# Controller.net
KiCad netlist of a schematic drawn in EAGLE
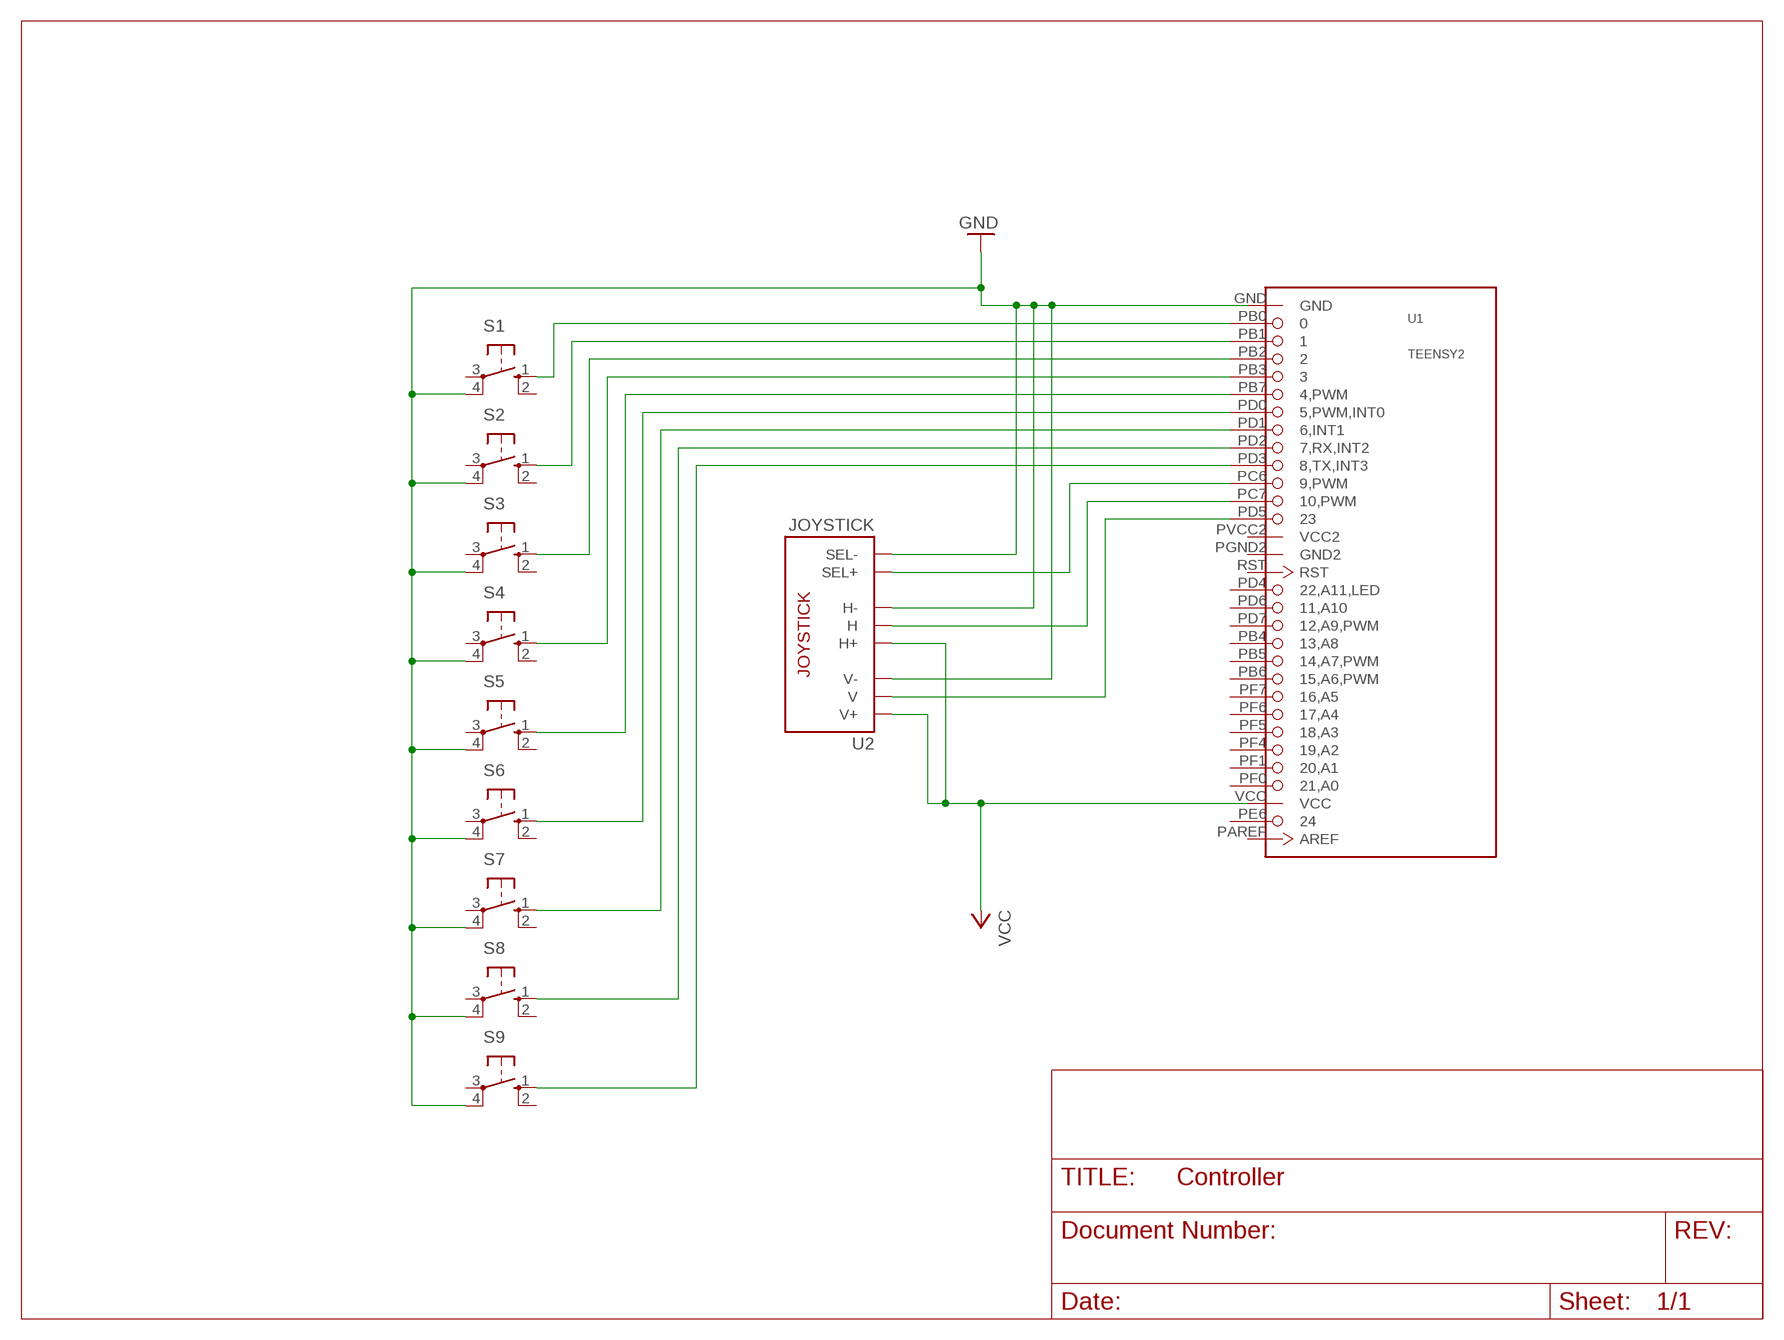
[diagram p0: schematic, sheet 1]

(export (version "E")
  (design (tool "Eeschema 10.0.6"))
  (components
    (comp (ref "S1")
      (value "10-XX")
      (footprint "eagle-import:B3F-10XX")
      (fields (field (name "MPN") "B3F-1000"))
      (libsource (lib "eagle-import") (part "10-XX"))
    )
    (comp (ref "S2")
      (value "10-XX")
      (footprint "eagle-import:B3F-10XX")
      (fields (field (name "MPN") "B3F-1000"))
      (libsource (lib "eagle-import") (part "10-XX"))
    )
    (comp (ref "S3")
      (value "10-XX")
      (footprint "eagle-import:B3F-10XX")
      (fields (field (name "MPN") "B3F-1000"))
      (libsource (lib "eagle-import") (part "10-XX"))
    )
    (comp (ref "S4")
      (value "10-XX")
      (footprint "eagle-import:B3F-10XX")
      (fields (field (name "MPN") "B3F-1000"))
      (libsource (lib "eagle-import") (part "10-XX"))
    )
    (comp (ref "S5")
      (value "10-XX")
      (footprint "eagle-import:B3F-10XX")
      (fields (field (name "MPN") "B3F-1000"))
      (libsource (lib "eagle-import") (part "10-XX"))
    )
    (comp (ref "S6")
      (value "10-XX")
      (footprint "eagle-import:B3F-10XX")
      (fields (field (name "MPN") "B3F-1000"))
      (libsource (lib "eagle-import") (part "10-XX"))
    )
    (comp (ref "S7")
      (value "10-XX")
      (footprint "eagle-import:B3F-10XX")
      (fields (field (name "MPN") "B3F-1000"))
      (libsource (lib "eagle-import") (part "10-XX"))
    )
    (comp (ref "S8")
      (value "10-XX")
      (footprint "eagle-import:B3F-10XX")
      (fields (field (name "MPN") "B3F-1000"))
      (libsource (lib "eagle-import") (part "10-XX"))
    )
    (comp (ref "S9")
      (value "10-XX")
      (footprint "eagle-import:B3F-10XX")
      (fields (field (name "MPN") "B3F-1000"))
      (libsource (lib "eagle-import") (part "10-XX"))
    )
    (comp (ref "U1")
      (value "TEENSY2")
      (footprint "eagle-import:TEENSY2")
      (libsource (lib "eagle-import") (part "TEENSY2-ARDUINO"))
    )
    (comp (ref "U2")
      (value "JOYSTICK")
      (footprint "eagle-import:JOYSTICK")
      (libsource (lib "eagle-import") (part "JOYSTICKPTH"))
    )
  )
  (nets
    (net (code "1") (name "/GND2") (class "Default")
      (node (ref "U1") (pin "PGND2") (pinfunction "GND2_PGND2") (pintype "power_in"))
    )
    (net (code "2") (name "/VCC2") (class "Default")
      (node (ref "U1") (pin "PVCC2") (pinfunction "VCC2_PVCC2") (pintype "power_in"))
    )
    (net (code "3") (name "GND") (class "Default")
      (node (ref "S1") (pin "4") (pinfunction "P1_4") (pintype "passive"))
      (node (ref "S2") (pin "4") (pinfunction "P1_4") (pintype "passive"))
      (node (ref "S3") (pin "4") (pinfunction "P1_4") (pintype "passive"))
      (node (ref "S4") (pin "4") (pinfunction "P1_4") (pintype "passive"))
      (node (ref "S5") (pin "4") (pinfunction "P1_4") (pintype "passive"))
      (node (ref "S6") (pin "4") (pinfunction "P1_4") (pintype "passive"))
      (node (ref "S7") (pin "4") (pinfunction "P1_4") (pintype "passive"))
      (node (ref "S8") (pin "4") (pinfunction "P1_4") (pintype "passive"))
      (node (ref "S9") (pin "4") (pinfunction "P1_4") (pintype "passive"))
      (node (ref "U1") (pin "GND") (pinfunction "GND_GND") (pintype "power_in"))
      (node (ref "U2") (pin "B2A") (pinfunction "SEL-_B2A") (pintype "bidirectional"))
      (node (ref "U2") (pin "H3") (pinfunction "H-_H3") (pintype "bidirectional"))
      (node (ref "U2") (pin "V3") (pinfunction "V-_V3") (pintype "bidirectional"))
    )
    (net (code "4") (name "Net-(S1-S)") (class "Default")
      (node (ref "S1") (pin "1") (pinfunction "S_1") (pintype "passive"))
      (node (ref "U1") (pin "PB0") (pinfunction "0_PB0") (pintype "bidirectional"))
    )
    (net (code "5") (name "Net-(S2-S)") (class "Default")
      (node (ref "S2") (pin "1") (pinfunction "S_1") (pintype "passive"))
      (node (ref "U1") (pin "PB1") (pinfunction "1_PB1") (pintype "bidirectional"))
    )
    (net (code "6") (name "Net-(S3-S)") (class "Default")
      (node (ref "S3") (pin "1") (pinfunction "S_1") (pintype "passive"))
      (node (ref "U1") (pin "PB2") (pinfunction "2_PB2") (pintype "bidirectional"))
    )
    (net (code "7") (name "Net-(S4-S)") (class "Default")
      (node (ref "S4") (pin "1") (pinfunction "S_1") (pintype "passive"))
      (node (ref "U1") (pin "PB3") (pinfunction "3_PB3") (pintype "bidirectional"))
    )
    (net (code "8") (name "Net-(S5-S)") (class "Default")
      (node (ref "S5") (pin "1") (pinfunction "S_1") (pintype "passive"))
      (node (ref "U1") (pin "PB7") (pinfunction "4,PWM_PB7") (pintype "bidirectional"))
    )
    (net (code "9") (name "Net-(S6-S)") (class "Default")
      (node (ref "S6") (pin "1") (pinfunction "S_1") (pintype "passive"))
      (node (ref "U1") (pin "PD0") (pinfunction "5,PWM,INT0_PD0") (pintype "bidirectional"))
    )
    (net (code "10") (name "Net-(S7-S)") (class "Default")
      (node (ref "S7") (pin "1") (pinfunction "S_1") (pintype "passive"))
      (node (ref "U1") (pin "PD1") (pinfunction "6,INT1_PD1") (pintype "bidirectional"))
    )
    (net (code "11") (name "Net-(S8-S)") (class "Default")
      (node (ref "S8") (pin "1") (pinfunction "S_1") (pintype "passive"))
      (node (ref "U1") (pin "PD2") (pinfunction "7,RX,INT2_PD2") (pintype "bidirectional"))
    )
    (net (code "12") (name "Net-(S9-S)") (class "Default")
      (node (ref "S9") (pin "1") (pinfunction "S_1") (pintype "passive"))
      (node (ref "U1") (pin "PD3") (pinfunction "8,TX,INT3_PD3") (pintype "bidirectional"))
    )
    (net (code "13") (name "Net-(U1-9,PWM)") (class "Default")
      (node (ref "U1") (pin "PC6") (pinfunction "9,PWM_PC6") (pintype "bidirectional"))
      (node (ref "U2") (pin "B1A") (pinfunction "SEL+_B1A") (pintype "bidirectional"))
    )
    (net (code "14") (name "Net-(U1-10,PWM)") (class "Default")
      (node (ref "U1") (pin "PC7") (pinfunction "10,PWM_PC7") (pintype "bidirectional"))
      (node (ref "U2") (pin "H2") (pinfunction "H_H2") (pintype "bidirectional"))
    )
    (net (code "15") (name "Net-(U1-23)") (class "Default")
      (node (ref "U1") (pin "PD5") (pinfunction "23_PD5") (pintype "bidirectional"))
      (node (ref "U2") (pin "V2") (pinfunction "V_V2") (pintype "bidirectional"))
    )
    (net (code "16") (name "VCC") (class "Default")
      (node (ref "U1") (pin "VCC") (pinfunction "VCC_VCC") (pintype "power_in"))
      (node (ref "U2") (pin "H1") (pinfunction "H+_H1") (pintype "bidirectional"))
      (node (ref "U2") (pin "V1") (pinfunction "V+_V1") (pintype "bidirectional"))
    )
    (net (code "17") (name "unconnected-(S1-P-Pad3)") (class "Default")
      (node (ref "S1") (pin "3") (pinfunction "P_3") (pintype "passive"))
    )
    (net (code "18") (name "unconnected-(S1-S1-Pad2)") (class "Default")
      (node (ref "S1") (pin "2") (pinfunction "S1_2") (pintype "passive"))
    )
    (net (code "19") (name "unconnected-(S2-P-Pad3)") (class "Default")
      (node (ref "S2") (pin "3") (pinfunction "P_3") (pintype "passive"))
    )
    (net (code "20") (name "unconnected-(S2-S1-Pad2)") (class "Default")
      (node (ref "S2") (pin "2") (pinfunction "S1_2") (pintype "passive"))
    )
    (net (code "21") (name "unconnected-(S3-P-Pad3)") (class "Default")
      (node (ref "S3") (pin "3") (pinfunction "P_3") (pintype "passive"))
    )
    (net (code "22") (name "unconnected-(S3-S1-Pad2)") (class "Default")
      (node (ref "S3") (pin "2") (pinfunction "S1_2") (pintype "passive"))
    )
    (net (code "23") (name "unconnected-(S4-P-Pad3)") (class "Default")
      (node (ref "S4") (pin "3") (pinfunction "P_3") (pintype "passive"))
    )
    (net (code "24") (name "unconnected-(S4-S1-Pad2)") (class "Default")
      (node (ref "S4") (pin "2") (pinfunction "S1_2") (pintype "passive"))
    )
    (net (code "25") (name "unconnected-(S5-P-Pad3)") (class "Default")
      (node (ref "S5") (pin "3") (pinfunction "P_3") (pintype "passive"))
    )
    (net (code "26") (name "unconnected-(S5-S1-Pad2)") (class "Default")
      (node (ref "S5") (pin "2") (pinfunction "S1_2") (pintype "passive"))
    )
    (net (code "27") (name "unconnected-(S6-P-Pad3)") (class "Default")
      (node (ref "S6") (pin "3") (pinfunction "P_3") (pintype "passive"))
    )
    (net (code "28") (name "unconnected-(S6-S1-Pad2)") (class "Default")
      (node (ref "S6") (pin "2") (pinfunction "S1_2") (pintype "passive"))
    )
    (net (code "29") (name "unconnected-(S7-P-Pad3)") (class "Default")
      (node (ref "S7") (pin "3") (pinfunction "P_3") (pintype "passive"))
    )
    (net (code "30") (name "unconnected-(S7-S1-Pad2)") (class "Default")
      (node (ref "S7") (pin "2") (pinfunction "S1_2") (pintype "passive"))
    )
    (net (code "31") (name "unconnected-(S8-P-Pad3)") (class "Default")
      (node (ref "S8") (pin "3") (pinfunction "P_3") (pintype "passive"))
    )
    (net (code "32") (name "unconnected-(S8-S1-Pad2)") (class "Default")
      (node (ref "S8") (pin "2") (pinfunction "S1_2") (pintype "passive"))
    )
    (net (code "33") (name "unconnected-(S9-P-Pad3)") (class "Default")
      (node (ref "S9") (pin "3") (pinfunction "P_3") (pintype "passive"))
    )
    (net (code "34") (name "unconnected-(S9-S1-Pad2)") (class "Default")
      (node (ref "S9") (pin "2") (pinfunction "S1_2") (pintype "passive"))
    )
    (net (code "35") (name "unconnected-(U1-11,A10-PadPD6)") (class "Default")
      (node (ref "U1") (pin "PD6") (pinfunction "11,A10_PD6") (pintype "bidirectional"))
    )
    (net (code "36") (name "unconnected-(U1-12,A9,PWM-PadPD7)") (class "Default")
      (node (ref "U1") (pin "PD7") (pinfunction "12,A9,PWM_PD7") (pintype "bidirectional"))
    )
    (net (code "37") (name "unconnected-(U1-13,A8-PadPB4)") (class "Default")
      (node (ref "U1") (pin "PB4") (pinfunction "13,A8_PB4") (pintype "bidirectional"))
    )
    (net (code "38") (name "unconnected-(U1-14,A7,PWM-PadPB5)") (class "Default")
      (node (ref "U1") (pin "PB5") (pinfunction "14,A7,PWM_PB5") (pintype "bidirectional"))
    )
    (net (code "39") (name "unconnected-(U1-15,A6,PWM-PadPB6)") (class "Default")
      (node (ref "U1") (pin "PB6") (pinfunction "15,A6,PWM_PB6") (pintype "bidirectional"))
    )
    (net (code "40") (name "unconnected-(U1-16,A5-PadPF7)") (class "Default")
      (node (ref "U1") (pin "PF7") (pinfunction "16,A5_PF7") (pintype "bidirectional"))
    )
    (net (code "41") (name "unconnected-(U1-17,A4-PadPF6)") (class "Default")
      (node (ref "U1") (pin "PF6") (pinfunction "17,A4_PF6") (pintype "bidirectional"))
    )
    (net (code "42") (name "unconnected-(U1-18,A3-PadPF5)") (class "Default")
      (node (ref "U1") (pin "PF5") (pinfunction "18,A3_PF5") (pintype "bidirectional"))
    )
    (net (code "43") (name "unconnected-(U1-19,A2-PadPF4)") (class "Default")
      (node (ref "U1") (pin "PF4") (pinfunction "19,A2_PF4") (pintype "bidirectional"))
    )
    (net (code "44") (name "unconnected-(U1-20,A1-PadPF1)") (class "Default")
      (node (ref "U1") (pin "PF1") (pinfunction "20,A1_PF1") (pintype "bidirectional"))
    )
    (net (code "45") (name "unconnected-(U1-21,A0-PadPF0)") (class "Default")
      (node (ref "U1") (pin "PF0") (pinfunction "21,A0_PF0") (pintype "bidirectional"))
    )
    (net (code "46") (name "unconnected-(U1-22,A11,LED-PadPD4)") (class "Default")
      (node (ref "U1") (pin "PD4") (pinfunction "22,A11,LED_PD4") (pintype "bidirectional"))
    )
    (net (code "47") (name "unconnected-(U1-24-PadPE6)") (class "Default")
      (node (ref "U1") (pin "PE6") (pinfunction "24_PE6") (pintype "bidirectional"))
    )
    (net (code "48") (name "unconnected-(U1-AREF-PadPAREF)") (class "Default")
      (node (ref "U1") (pin "PAREF") (pinfunction "AREF_PAREF") (pintype "input"))
    )
    (net (code "49") (name "unconnected-(U1-PadRST)") (class "Default")
      (node (ref "U1") (pin "RST") (pinfunction "RST_RST") (pintype "input"))
    )
  )
)
